# heaters.net
KiCad netlist of a schematic drawn in EAGLE
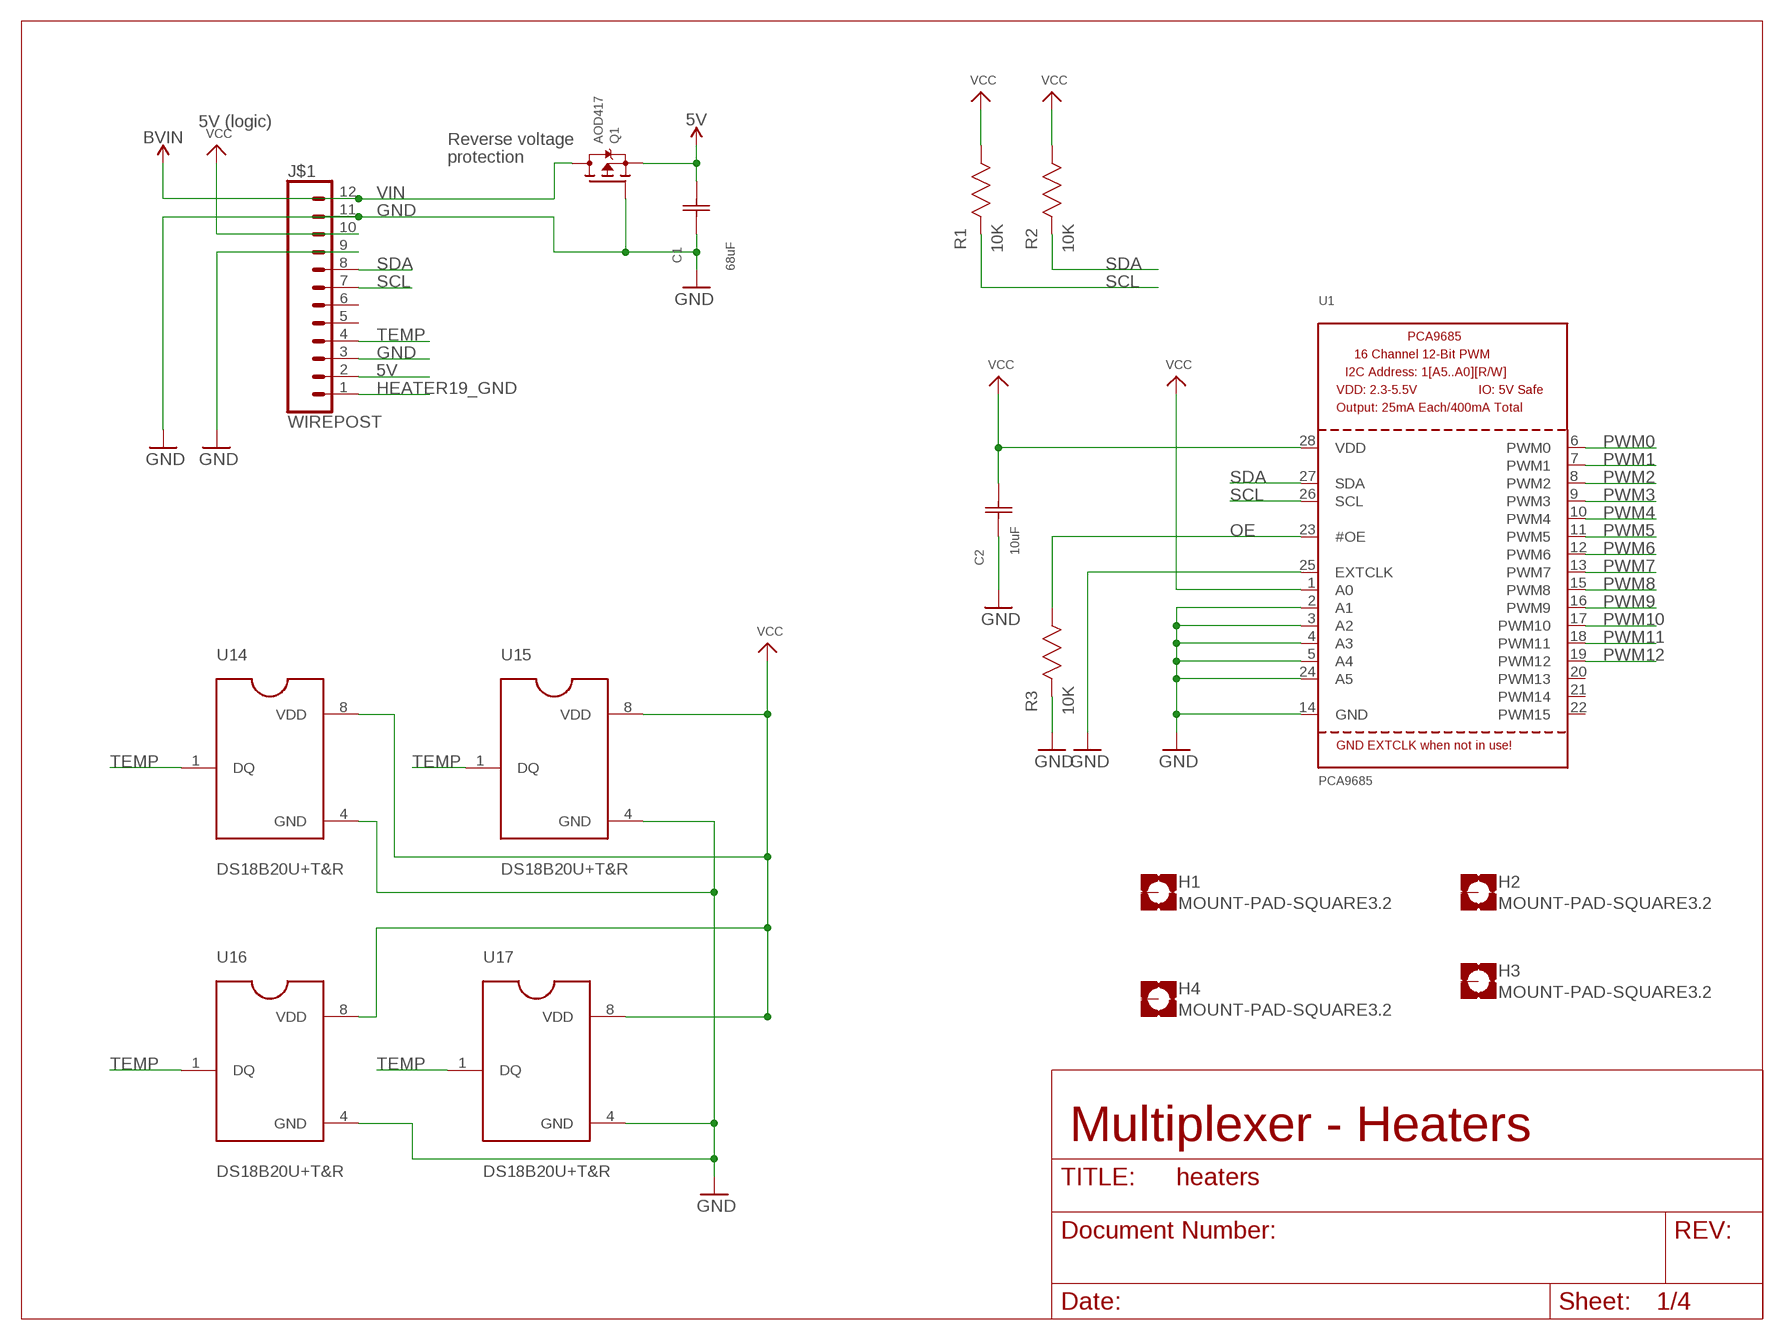
[diagram p0: schematic, sheet 1]
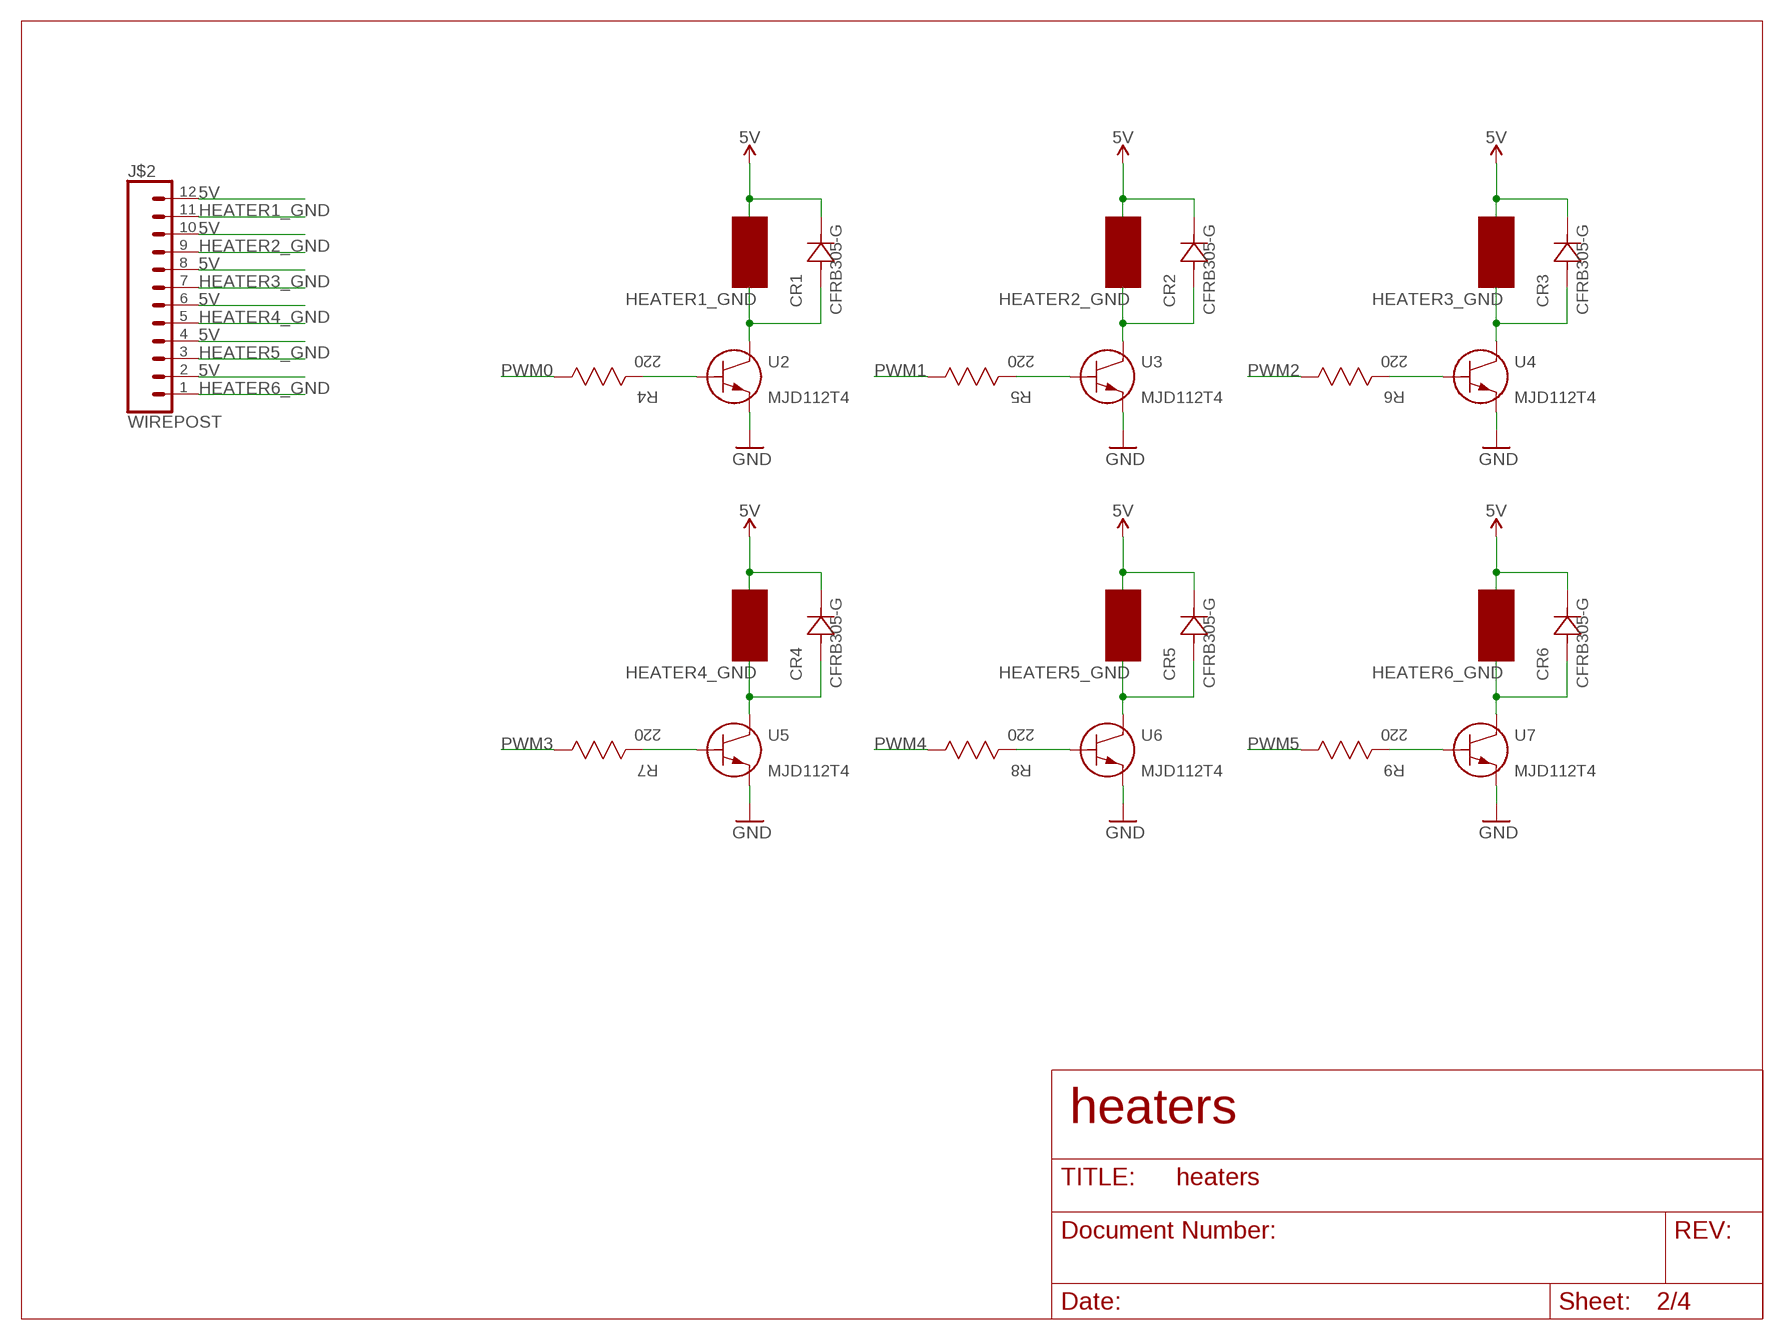
[diagram p1: schematic, sheet 2]
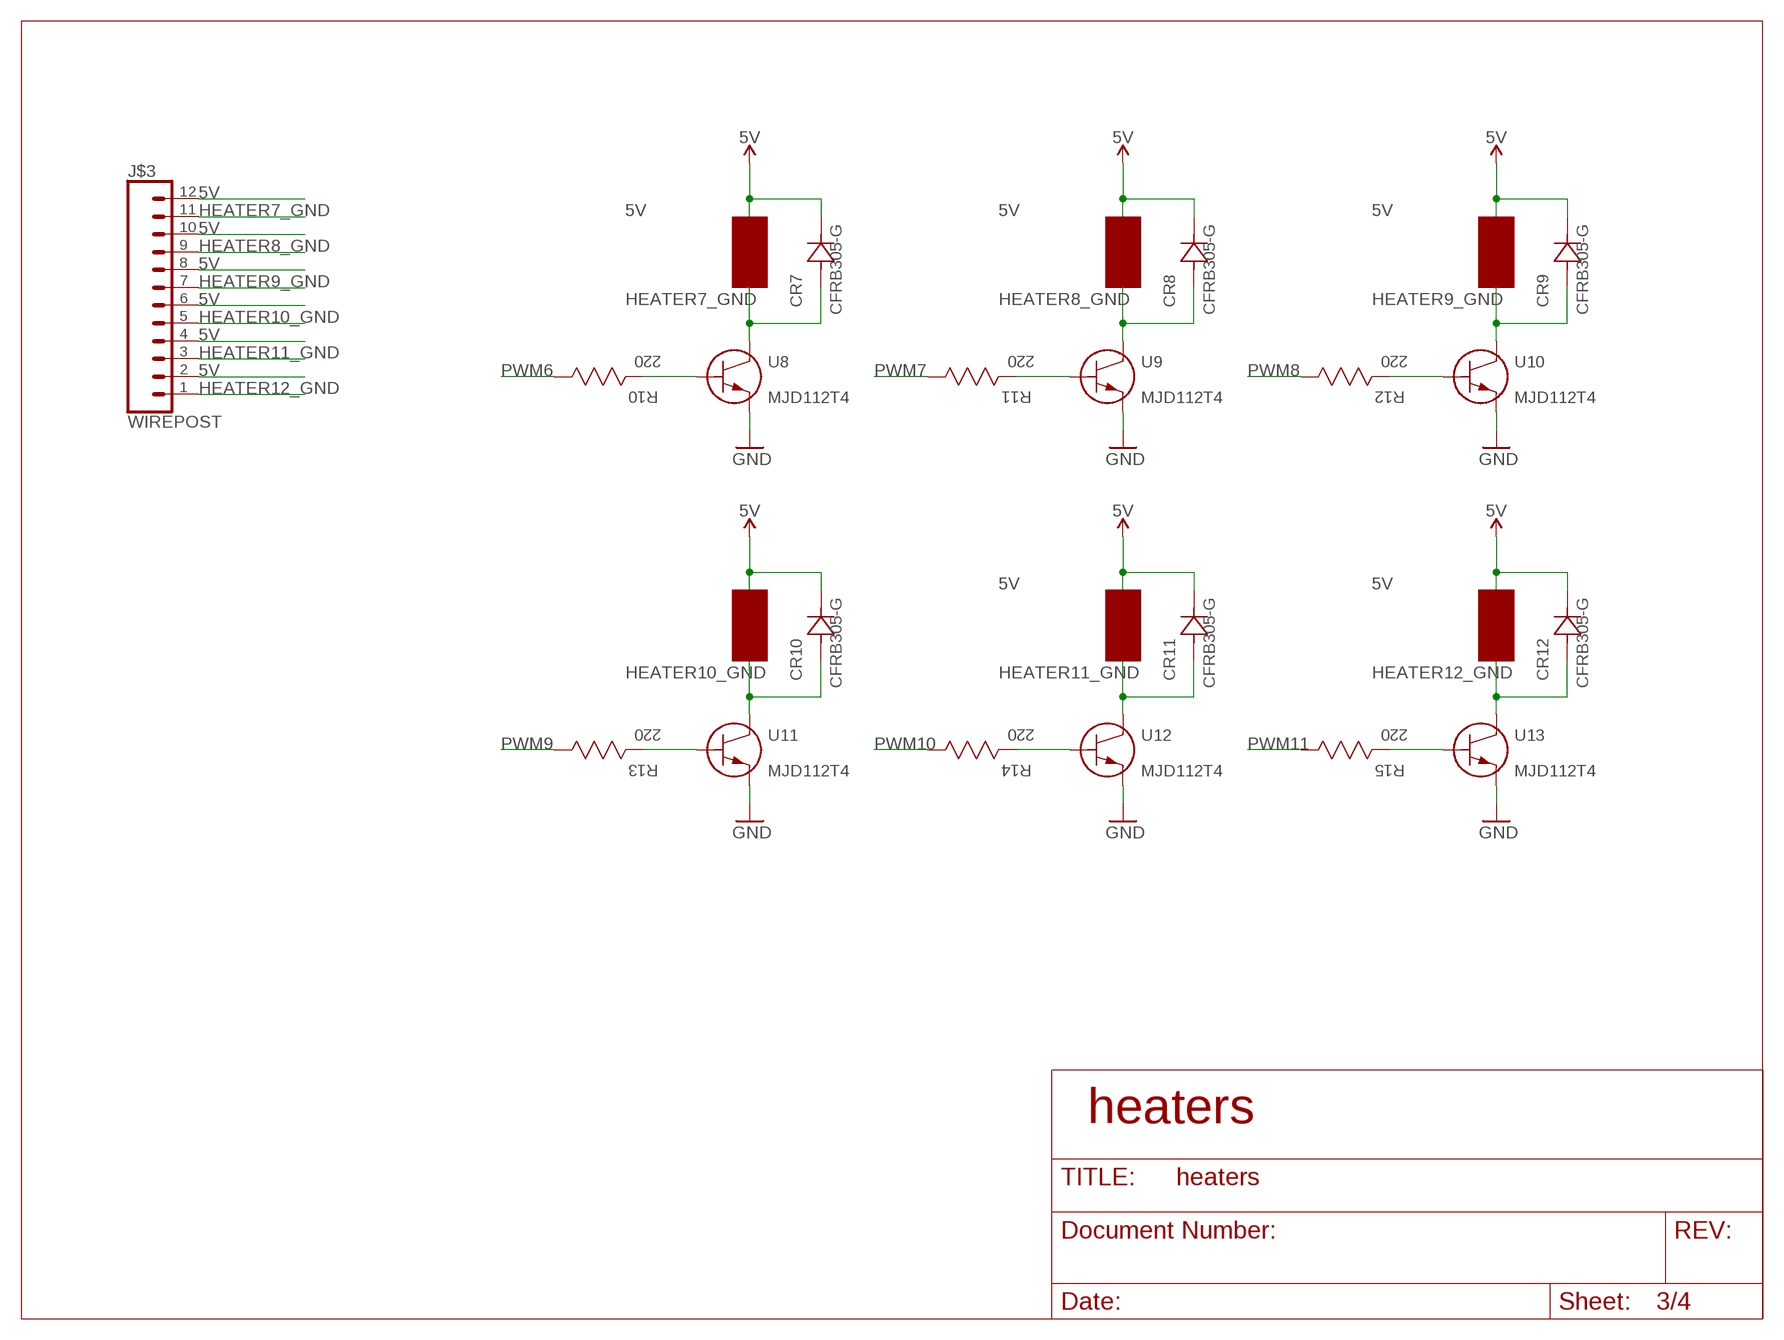
[diagram p2: schematic, sheet 3]
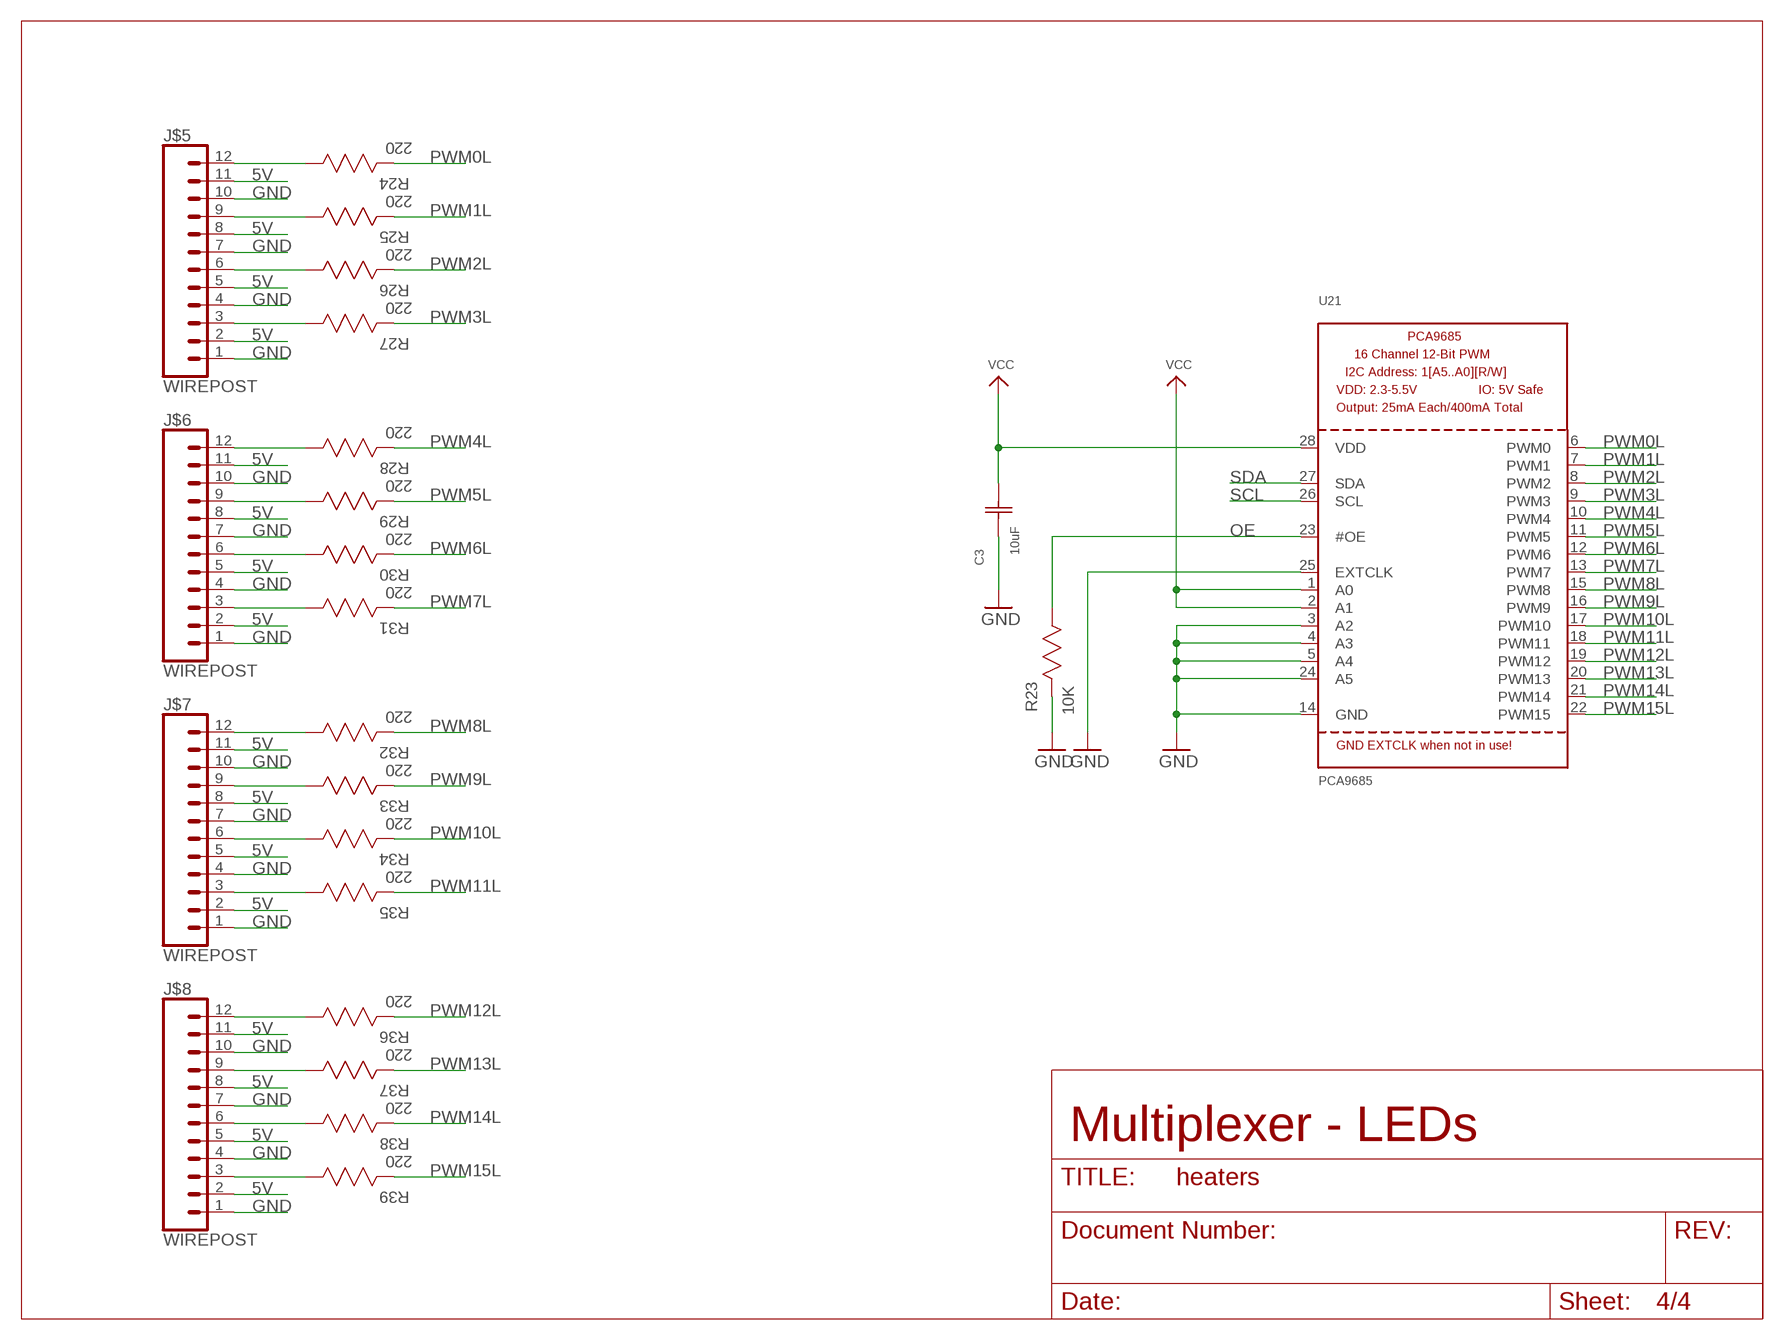
[diagram p3: schematic, sheet 4]

(export (version "E")
  (design (tool "Eeschema 10.0.6"))
  (components
    (comp (ref "C1")
      (value "68uF")
      (footprint "eagle-import:CAP_5750")
      (fields (field (name "MANUFACTURER_PART_NUMBER") "C5750X5R1A686M230KA"))
      (libsource (lib "eagle-import") (part "C5750X5R1A686M230KA"))
    )
    (comp (ref "C2")
      (value "10uF")
      (footprint "eagle-import:1206")
      (fields (field (name "MANUFACTURER_PART_NUMBER") "1206YC106KAT2A"))
      (libsource (lib "eagle-import") (part "1206YC106KAT2A"))
    )
    (comp (ref "H1")
      (value "MOUNT-PAD-SQUARE3.2")
      (footprint "eagle-import:3,2-PAD-SQUARE")
      (libsource (lib "eagle-import") (part "MOUNT-PAD-SQUARE3.2"))
    )
    (comp (ref "H2")
      (value "MOUNT-PAD-SQUARE3.2")
      (footprint "eagle-import:3,2-PAD-SQUARE")
      (libsource (lib "eagle-import") (part "MOUNT-PAD-SQUARE3.2"))
    )
    (comp (ref "H3")
      (value "MOUNT-PAD-SQUARE3.2")
      (footprint "eagle-import:3,2-PAD-SQUARE")
      (libsource (lib "eagle-import") (part "MOUNT-PAD-SQUARE3.2"))
    )
    (comp (ref "H4")
      (value "MOUNT-PAD-SQUARE3.2")
      (footprint "eagle-import:3,2-PAD-SQUARE")
      (libsource (lib "eagle-import") (part "MOUNT-PAD-SQUARE3.2"))
    )
    (comp (ref "J$1")
      (value "WIREPOST")
      (footprint "eagle-import:WIREWRAPPOST")
      (libsource (lib "eagle-import") (part "WIREPOST"))
    )
    (comp (ref "Q1")
      (value "AOD417")
      (footprint "eagle-import:TO252")
      (libsource (lib "eagle-import") (part "MOSFET-PTO252"))
    )
    (comp (ref "R1")
      (value "10K")
      (footprint "eagle-import:RC0603N")
      (fields (field (name "MANUFACTURER_PART_NUMBER") "RC0603JR0710KL"))
      (libsource (lib "eagle-import") (part "RC0603JR-0710KL"))
    )
    (comp (ref "R2")
      (value "10K")
      (footprint "eagle-import:RC0603N")
      (fields (field (name "MANUFACTURER_PART_NUMBER") "RC0603JR0710KL"))
      (libsource (lib "eagle-import") (part "RC0603JR-0710KL"))
    )
    (comp (ref "R3")
      (value "10K")
      (footprint "eagle-import:RC0603N")
      (fields (field (name "MANUFACTURER_PART_NUMBER") "RC0603JR0710KL"))
      (libsource (lib "eagle-import") (part "RC0603JR-0710KL"))
    )
    (comp (ref "U1")
      (value "PCA9685")
      (footprint "eagle-import:TSSOP28")
      (libsource (lib "eagle-import") (part "PCA9685"))
    )
    (comp (ref "U14")
      (value "DS18B20U+T&R")
      (footprint "eagle-import:SOP65P500X110-8N")
      (fields (field (name "MF") "Maxim Integrated") (field (name "MP") "DS18B20U+T&amp;R"))
      (libsource (lib "eagle-import") (part "DS18B20U+T&R"))
    )
    (comp (ref "U15")
      (value "DS18B20U+T&R")
      (footprint "eagle-import:SOP65P500X110-8N")
      (fields (field (name "MF") "Maxim Integrated") (field (name "MP") "DS18B20U+T&amp;R"))
      (libsource (lib "eagle-import") (part "DS18B20U+T&R"))
    )
    (comp (ref "U16")
      (value "DS18B20U+T&R")
      (footprint "eagle-import:SOP65P500X110-8N")
      (fields (field (name "MF") "Maxim Integrated") (field (name "MP") "DS18B20U+T&amp;R"))
      (libsource (lib "eagle-import") (part "DS18B20U+T&R"))
    )
    (comp (ref "U17")
      (value "DS18B20U+T&R")
      (footprint "eagle-import:SOP65P500X110-8N")
      (fields (field (name "MF") "Maxim Integrated") (field (name "MP") "DS18B20U+T&amp;R"))
      (libsource (lib "eagle-import") (part "DS18B20U+T&R"))
    )
    (comp (ref "C3")
      (value "10uF")
      (footprint "eagle-import:1206")
      (fields (field (name "MANUFACTURER_PART_NUMBER") "1206YC106KAT2A"))
      (libsource (lib "eagle-import") (part "1206YC106KAT2A"))
    )
    (comp (ref "J$5")
      (value "WIREPOST")
      (footprint "eagle-import:WIREWRAPPOST")
      (libsource (lib "eagle-import") (part "WIREPOST"))
    )
    (comp (ref "J$6")
      (value "WIREPOST")
      (footprint "eagle-import:WIREWRAPPOST")
      (libsource (lib "eagle-import") (part "WIREPOST"))
    )
    (comp (ref "J$7")
      (value "WIREPOST")
      (footprint "eagle-import:WIREWRAPPOST")
      (libsource (lib "eagle-import") (part "WIREPOST"))
    )
    (comp (ref "J$8")
      (value "WIREPOST")
      (footprint "eagle-import:WIREWRAPPOST")
      (libsource (lib "eagle-import") (part "WIREPOST"))
    )
    (comp (ref "R23")
      (value "10K")
      (footprint "eagle-import:RC0603N")
      (fields (field (name "MANUFACTURER_PART_NUMBER") "RC0603JR0710KL"))
      (libsource (lib "eagle-import") (part "RC0603JR-0710KL"))
    )
    (comp (ref "R24")
      (value "220")
      (footprint "eagle-import:RC0603N")
      (fields (field (name "MANUFACTURER_PART_NUMBER") "RC0603JR07220RL"))
      (libsource (lib "eagle-import") (part "RC0603JR-07220RL"))
    )
    (comp (ref "R25")
      (value "220")
      (footprint "eagle-import:RC0603N")
      (fields (field (name "MANUFACTURER_PART_NUMBER") "RC0603JR07220RL"))
      (libsource (lib "eagle-import") (part "RC0603JR-07220RL"))
    )
    (comp (ref "R26")
      (value "220")
      (footprint "eagle-import:RC0603N")
      (fields (field (name "MANUFACTURER_PART_NUMBER") "RC0603JR07220RL"))
      (libsource (lib "eagle-import") (part "RC0603JR-07220RL"))
    )
    (comp (ref "R27")
      (value "220")
      (footprint "eagle-import:RC0603N")
      (fields (field (name "MANUFACTURER_PART_NUMBER") "RC0603JR07220RL"))
      (libsource (lib "eagle-import") (part "RC0603JR-07220RL"))
    )
    (comp (ref "R28")
      (value "220")
      (footprint "eagle-import:RC0603N")
      (fields (field (name "MANUFACTURER_PART_NUMBER") "RC0603JR07220RL"))
      (libsource (lib "eagle-import") (part "RC0603JR-07220RL"))
    )
    (comp (ref "R29")
      (value "220")
      (footprint "eagle-import:RC0603N")
      (fields (field (name "MANUFACTURER_PART_NUMBER") "RC0603JR07220RL"))
      (libsource (lib "eagle-import") (part "RC0603JR-07220RL"))
    )
    (comp (ref "R30")
      (value "220")
      (footprint "eagle-import:RC0603N")
      (fields (field (name "MANUFACTURER_PART_NUMBER") "RC0603JR07220RL"))
      (libsource (lib "eagle-import") (part "RC0603JR-07220RL"))
    )
    (comp (ref "R31")
      (value "220")
      (footprint "eagle-import:RC0603N")
      (fields (field (name "MANUFACTURER_PART_NUMBER") "RC0603JR07220RL"))
      (libsource (lib "eagle-import") (part "RC0603JR-07220RL"))
    )
    (comp (ref "R32")
      (value "220")
      (footprint "eagle-import:RC0603N")
      (fields (field (name "MANUFACTURER_PART_NUMBER") "RC0603JR07220RL"))
      (libsource (lib "eagle-import") (part "RC0603JR-07220RL"))
    )
    (comp (ref "R33")
      (value "220")
      (footprint "eagle-import:RC0603N")
      (fields (field (name "MANUFACTURER_PART_NUMBER") "RC0603JR07220RL"))
      (libsource (lib "eagle-import") (part "RC0603JR-07220RL"))
    )
    (comp (ref "R34")
      (value "220")
      (footprint "eagle-import:RC0603N")
      (fields (field (name "MANUFACTURER_PART_NUMBER") "RC0603JR07220RL"))
      (libsource (lib "eagle-import") (part "RC0603JR-07220RL"))
    )
    (comp (ref "R35")
      (value "220")
      (footprint "eagle-import:RC0603N")
      (fields (field (name "MANUFACTURER_PART_NUMBER") "RC0603JR07220RL"))
      (libsource (lib "eagle-import") (part "RC0603JR-07220RL"))
    )
    (comp (ref "R36")
      (value "220")
      (footprint "eagle-import:RC0603N")
      (fields (field (name "MANUFACTURER_PART_NUMBER") "RC0603JR07220RL"))
      (libsource (lib "eagle-import") (part "RC0603JR-07220RL"))
    )
    (comp (ref "R37")
      (value "220")
      (footprint "eagle-import:RC0603N")
      (fields (field (name "MANUFACTURER_PART_NUMBER") "RC0603JR07220RL"))
      (libsource (lib "eagle-import") (part "RC0603JR-07220RL"))
    )
    (comp (ref "R38")
      (value "220")
      (footprint "eagle-import:RC0603N")
      (fields (field (name "MANUFACTURER_PART_NUMBER") "RC0603JR07220RL"))
      (libsource (lib "eagle-import") (part "RC0603JR-07220RL"))
    )
    (comp (ref "R39")
      (value "220")
      (footprint "eagle-import:RC0603N")
      (fields (field (name "MANUFACTURER_PART_NUMBER") "RC0603JR07220RL"))
      (libsource (lib "eagle-import") (part "RC0603JR-07220RL"))
    )
    (comp (ref "U21")
      (value "PCA9685")
      (footprint "eagle-import:TSSOP28")
      (libsource (lib "eagle-import") (part "PCA9685"))
    )
    (comp (ref "CR7")
      (value "CFRB305-G")
      (footprint "eagle-import:CFRB-G")
      (fields (field (name "MANUFACTURER_PART_NUMBER") "CFRB305G"))
      (libsource (lib "eagle-import") (part "CFRB305-G"))
    )
    (comp (ref "CR8")
      (value "CFRB305-G")
      (footprint "eagle-import:CFRB-G")
      (fields (field (name "MANUFACTURER_PART_NUMBER") "CFRB305G"))
      (libsource (lib "eagle-import") (part "CFRB305-G"))
    )
    (comp (ref "CR9")
      (value "CFRB305-G")
      (footprint "eagle-import:CFRB-G")
      (fields (field (name "MANUFACTURER_PART_NUMBER") "CFRB305G"))
      (libsource (lib "eagle-import") (part "CFRB305-G"))
    )
    (comp (ref "CR10")
      (value "CFRB305-G")
      (footprint "eagle-import:CFRB-G")
      (fields (field (name "MANUFACTURER_PART_NUMBER") "CFRB305G"))
      (libsource (lib "eagle-import") (part "CFRB305-G"))
    )
    (comp (ref "CR11")
      (value "CFRB305-G")
      (footprint "eagle-import:CFRB-G")
      (fields (field (name "MANUFACTURER_PART_NUMBER") "CFRB305G"))
      (libsource (lib "eagle-import") (part "CFRB305-G"))
    )
    (comp (ref "CR12")
      (value "CFRB305-G")
      (footprint "eagle-import:CFRB-G")
      (fields (field (name "MANUFACTURER_PART_NUMBER") "CFRB305G"))
      (libsource (lib "eagle-import") (part "CFRB305-G"))
    )
    (comp (ref "J$3")
      (value "WIREPOST")
      (footprint "eagle-import:WIREWRAPPOST")
      (libsource (lib "eagle-import") (part "WIREPOST"))
    )
    (comp (ref "R10")
      (value "220")
      (footprint "eagle-import:RC0603N")
      (fields (field (name "MANUFACTURER_PART_NUMBER") "RC0603JR07220RL"))
      (libsource (lib "eagle-import") (part "RC0603JR-07220RL"))
    )
    (comp (ref "R11")
      (value "220")
      (footprint "eagle-import:RC0603N")
      (fields (field (name "MANUFACTURER_PART_NUMBER") "RC0603JR07220RL"))
      (libsource (lib "eagle-import") (part "RC0603JR-07220RL"))
    )
    (comp (ref "R12")
      (value "220")
      (footprint "eagle-import:RC0603N")
      (fields (field (name "MANUFACTURER_PART_NUMBER") "RC0603JR07220RL"))
      (libsource (lib "eagle-import") (part "RC0603JR-07220RL"))
    )
    (comp (ref "R13")
      (value "220")
      (footprint "eagle-import:RC0603N")
      (fields (field (name "MANUFACTURER_PART_NUMBER") "RC0603JR07220RL"))
      (libsource (lib "eagle-import") (part "RC0603JR-07220RL"))
    )
    (comp (ref "R14")
      (value "220")
      (footprint "eagle-import:RC0603N")
      (fields (field (name "MANUFACTURER_PART_NUMBER") "RC0603JR07220RL"))
      (libsource (lib "eagle-import") (part "RC0603JR-07220RL"))
    )
    (comp (ref "R15")
      (value "220")
      (footprint "eagle-import:RC0603N")
      (fields (field (name "MANUFACTURER_PART_NUMBER") "RC0603JR07220RL"))
      (libsource (lib "eagle-import") (part "RC0603JR-07220RL"))
    )
    (comp (ref "U8")
      (value "MJD112T4")
      (footprint "eagle-import:DPAK")
      (libsource (lib "eagle-import") (part "MJD112T4"))
    )
    (comp (ref "U9")
      (value "MJD112T4")
      (footprint "eagle-import:DPAK")
      (libsource (lib "eagle-import") (part "MJD112T4"))
    )
    (comp (ref "U10")
      (value "MJD112T4")
      (footprint "eagle-import:DPAK")
      (libsource (lib "eagle-import") (part "MJD112T4"))
    )
    (comp (ref "U11")
      (value "MJD112T4")
      (footprint "eagle-import:DPAK")
      (libsource (lib "eagle-import") (part "MJD112T4"))
    )
    (comp (ref "U12")
      (value "MJD112T4")
      (footprint "eagle-import:DPAK")
      (libsource (lib "eagle-import") (part "MJD112T4"))
    )
    (comp (ref "U13")
      (value "MJD112T4")
      (footprint "eagle-import:DPAK")
      (libsource (lib "eagle-import") (part "MJD112T4"))
    )
    (comp (ref "CR1")
      (value "CFRB305-G")
      (footprint "eagle-import:CFRB-G")
      (fields (field (name "MANUFACTURER_PART_NUMBER") "CFRB305G"))
      (libsource (lib "eagle-import") (part "CFRB305-G"))
    )
    (comp (ref "CR2")
      (value "CFRB305-G")
      (footprint "eagle-import:CFRB-G")
      (fields (field (name "MANUFACTURER_PART_NUMBER") "CFRB305G"))
      (libsource (lib "eagle-import") (part "CFRB305-G"))
    )
    (comp (ref "CR3")
      (value "CFRB305-G")
      (footprint "eagle-import:CFRB-G")
      (fields (field (name "MANUFACTURER_PART_NUMBER") "CFRB305G"))
      (libsource (lib "eagle-import") (part "CFRB305-G"))
    )
    (comp (ref "CR4")
      (value "CFRB305-G")
      (footprint "eagle-import:CFRB-G")
      (fields (field (name "MANUFACTURER_PART_NUMBER") "CFRB305G"))
      (libsource (lib "eagle-import") (part "CFRB305-G"))
    )
    (comp (ref "CR5")
      (value "CFRB305-G")
      (footprint "eagle-import:CFRB-G")
      (fields (field (name "MANUFACTURER_PART_NUMBER") "CFRB305G"))
      (libsource (lib "eagle-import") (part "CFRB305-G"))
    )
    (comp (ref "CR6")
      (value "CFRB305-G")
      (footprint "eagle-import:CFRB-G")
      (fields (field (name "MANUFACTURER_PART_NUMBER") "CFRB305G"))
      (libsource (lib "eagle-import") (part "CFRB305-G"))
    )
    (comp (ref "J$2")
      (value "WIREPOST")
      (footprint "eagle-import:WIREWRAPPOST")
      (libsource (lib "eagle-import") (part "WIREPOST"))
    )
    (comp (ref "R4")
      (value "220")
      (footprint "eagle-import:RC0603N")
      (fields (field (name "MANUFACTURER_PART_NUMBER") "RC0603JR07220RL"))
      (libsource (lib "eagle-import") (part "RC0603JR-07220RL"))
    )
    (comp (ref "R5")
      (value "220")
      (footprint "eagle-import:RC0603N")
      (fields (field (name "MANUFACTURER_PART_NUMBER") "RC0603JR07220RL"))
      (libsource (lib "eagle-import") (part "RC0603JR-07220RL"))
    )
    (comp (ref "R6")
      (value "220")
      (footprint "eagle-import:RC0603N")
      (fields (field (name "MANUFACTURER_PART_NUMBER") "RC0603JR07220RL"))
      (libsource (lib "eagle-import") (part "RC0603JR-07220RL"))
    )
    (comp (ref "R7")
      (value "220")
      (footprint "eagle-import:RC0603N")
      (fields (field (name "MANUFACTURER_PART_NUMBER") "RC0603JR07220RL"))
      (libsource (lib "eagle-import") (part "RC0603JR-07220RL"))
    )
    (comp (ref "R8")
      (value "220")
      (footprint "eagle-import:RC0603N")
      (fields (field (name "MANUFACTURER_PART_NUMBER") "RC0603JR07220RL"))
      (libsource (lib "eagle-import") (part "RC0603JR-07220RL"))
    )
    (comp (ref "R9")
      (value "220")
      (footprint "eagle-import:RC0603N")
      (fields (field (name "MANUFACTURER_PART_NUMBER") "RC0603JR07220RL"))
      (libsource (lib "eagle-import") (part "RC0603JR-07220RL"))
    )
    (comp (ref "U2")
      (value "MJD112T4")
      (footprint "eagle-import:DPAK")
      (libsource (lib "eagle-import") (part "MJD112T4"))
    )
    (comp (ref "U3")
      (value "MJD112T4")
      (footprint "eagle-import:DPAK")
      (libsource (lib "eagle-import") (part "MJD112T4"))
    )
    (comp (ref "U4")
      (value "MJD112T4")
      (footprint "eagle-import:DPAK")
      (libsource (lib "eagle-import") (part "MJD112T4"))
    )
    (comp (ref "U5")
      (value "MJD112T4")
      (footprint "eagle-import:DPAK")
      (libsource (lib "eagle-import") (part "MJD112T4"))
    )
    (comp (ref "U6")
      (value "MJD112T4")
      (footprint "eagle-import:DPAK")
      (libsource (lib "eagle-import") (part "MJD112T4"))
    )
    (comp (ref "U7")
      (value "MJD112T4")
      (footprint "eagle-import:DPAK")
      (libsource (lib "eagle-import") (part "MJD112T4"))
    )
  )
  (nets
    (net (code "1") (name "5V") (class "Default")
      (node (ref "C1") (pin "2") (pinfunction "22_2") (pintype "passive"))
      (node (ref "CR1") (pin "1") (pinfunction "2_1") (pintype "passive"))
      (node (ref "CR10") (pin "1") (pinfunction "2_1") (pintype "passive"))
      (node (ref "CR11") (pin "1") (pinfunction "2_1") (pintype "passive"))
      (node (ref "CR12") (pin "1") (pinfunction "2_1") (pintype "passive"))
      (node (ref "CR2") (pin "1") (pinfunction "2_1") (pintype "passive"))
      (node (ref "CR3") (pin "1") (pinfunction "2_1") (pintype "passive"))
      (node (ref "CR4") (pin "1") (pinfunction "2_1") (pintype "passive"))
      (node (ref "CR5") (pin "1") (pinfunction "2_1") (pintype "passive"))
      (node (ref "CR6") (pin "1") (pinfunction "2_1") (pintype "passive"))
      (node (ref "CR7") (pin "1") (pinfunction "2_1") (pintype "passive"))
      (node (ref "CR8") (pin "1") (pinfunction "2_1") (pintype "passive"))
      (node (ref "CR9") (pin "1") (pinfunction "2_1") (pintype "passive"))
      (node (ref "J$1") (pin "2") (pinfunction "2_2") (pintype "passive"))
      (node (ref "J$2") (pin "10") (pinfunction "10_10") (pintype "passive"))
      (node (ref "J$2") (pin "12") (pinfunction "12_12") (pintype "passive"))
      (node (ref "J$2") (pin "2") (pinfunction "2_2") (pintype "passive"))
      (node (ref "J$2") (pin "4") (pinfunction "4_4") (pintype "passive"))
      (node (ref "J$2") (pin "6") (pinfunction "6_6") (pintype "passive"))
      (node (ref "J$2") (pin "8") (pinfunction "8_8") (pintype "passive"))
      (node (ref "J$3") (pin "10") (pinfunction "10_10") (pintype "passive"))
      (node (ref "J$3") (pin "12") (pinfunction "12_12") (pintype "passive"))
      (node (ref "J$3") (pin "2") (pinfunction "2_2") (pintype "passive"))
      (node (ref "J$3") (pin "4") (pinfunction "4_4") (pintype "passive"))
      (node (ref "J$3") (pin "6") (pinfunction "6_6") (pintype "passive"))
      (node (ref "J$3") (pin "8") (pinfunction "8_8") (pintype "passive"))
      (node (ref "J$5") (pin "11") (pinfunction "11_11") (pintype "passive"))
      (node (ref "J$5") (pin "2") (pinfunction "2_2") (pintype "passive"))
      (node (ref "J$5") (pin "5") (pinfunction "5_5") (pintype "passive"))
      (node (ref "J$5") (pin "8") (pinfunction "8_8") (pintype "passive"))
      (node (ref "J$6") (pin "11") (pinfunction "11_11") (pintype "passive"))
      (node (ref "J$6") (pin "2") (pinfunction "2_2") (pintype "passive"))
      (node (ref "J$6") (pin "5") (pinfunction "5_5") (pintype "passive"))
      (node (ref "J$6") (pin "8") (pinfunction "8_8") (pintype "passive"))
      (node (ref "J$7") (pin "11") (pinfunction "11_11") (pintype "passive"))
      (node (ref "J$7") (pin "2") (pinfunction "2_2") (pintype "passive"))
      (node (ref "J$7") (pin "5") (pinfunction "5_5") (pintype "passive"))
      (node (ref "J$7") (pin "8") (pinfunction "8_8") (pintype "passive"))
      (node (ref "J$8") (pin "11") (pinfunction "11_11") (pintype "passive"))
      (node (ref "J$8") (pin "2") (pinfunction "2_2") (pintype "passive"))
      (node (ref "J$8") (pin "5") (pinfunction "5_5") (pintype "passive"))
      (node (ref "J$8") (pin "8") (pinfunction "8_8") (pintype "passive"))
      (node (ref "Q1") (pin "2") (pinfunction "S_2") (pintype "passive"))
    )
    (net (code "2") (name "GND") (class "Default")
      (node (ref "C1") (pin "1") (pinfunction "11_1") (pintype "passive"))
      (node (ref "C2") (pin "1") (pinfunction "1_1") (pintype "passive"))
      (node (ref "C3") (pin "1") (pinfunction "1_1") (pintype "passive"))
      (node (ref "J$1") (pin "11") (pinfunction "11_11") (pintype "passive"))
      (node (ref "J$1") (pin "3") (pinfunction "3_3") (pintype "passive"))
      (node (ref "J$1") (pin "9") (pinfunction "9_9") (pintype "passive"))
      (node (ref "J$5") (pin "1") (pinfunction "1_1") (pintype "passive"))
      (node (ref "J$5") (pin "10") (pinfunction "10_10") (pintype "passive"))
      (node (ref "J$5") (pin "4") (pinfunction "4_4") (pintype "passive"))
      (node (ref "J$5") (pin "7") (pinfunction "7_7") (pintype "passive"))
      (node (ref "J$6") (pin "1") (pinfunction "1_1") (pintype "passive"))
      (node (ref "J$6") (pin "10") (pinfunction "10_10") (pintype "passive"))
      (node (ref "J$6") (pin "4") (pinfunction "4_4") (pintype "passive"))
      (node (ref "J$6") (pin "7") (pinfunction "7_7") (pintype "passive"))
      (node (ref "J$7") (pin "1") (pinfunction "1_1") (pintype "passive"))
      (node (ref "J$7") (pin "10") (pinfunction "10_10") (pintype "passive"))
      (node (ref "J$7") (pin "4") (pinfunction "4_4") (pintype "passive"))
      (node (ref "J$7") (pin "7") (pinfunction "7_7") (pintype "passive"))
      (node (ref "J$8") (pin "1") (pinfunction "1_1") (pintype "passive"))
      (node (ref "J$8") (pin "10") (pinfunction "10_10") (pintype "passive"))
      (node (ref "J$8") (pin "4") (pinfunction "4_4") (pintype "passive"))
      (node (ref "J$8") (pin "7") (pinfunction "7_7") (pintype "passive"))
      (node (ref "Q1") (pin "1") (pinfunction "G_1") (pintype "passive"))
      (node (ref "R23") (pin "2") (pinfunction "22_2") (pintype "passive"))
      (node (ref "R3") (pin "2") (pinfunction "22_2") (pintype "passive"))
      (node (ref "U1") (pin "14") (pinfunction "GND_14") (pintype "power_in"))
      (node (ref "U1") (pin "2") (pinfunction "A1_2") (pintype "bidirectional"))
      (node (ref "U1") (pin "24") (pinfunction "A5_24") (pintype "bidirectional"))
      (node (ref "U1") (pin "25") (pinfunction "EXTCLK_25") (pintype "input"))
      (node (ref "U1") (pin "3") (pinfunction "A2_3") (pintype "bidirectional"))
      (node (ref "U1") (pin "4") (pinfunction "A3_4") (pintype "bidirectional"))
      (node (ref "U1") (pin "5") (pinfunction "A4_5") (pintype "bidirectional"))
      (node (ref "U10") (pin "2") (pinfunction "E2_2") (pintype "passive"))
      (node (ref "U11") (pin "2") (pinfunction "E2_2") (pintype "passive"))
      (node (ref "U12") (pin "2") (pinfunction "E2_2") (pintype "passive"))
      (node (ref "U13") (pin "2") (pinfunction "E2_2") (pintype "passive"))
      (node (ref "U14") (pin "4") (pinfunction "GND_4") (pintype "passive"))
      (node (ref "U15") (pin "4") (pinfunction "GND_4") (pintype "passive"))
      (node (ref "U16") (pin "4") (pinfunction "GND_4") (pintype "passive"))
      (node (ref "U17") (pin "4") (pinfunction "GND_4") (pintype "passive"))
      (node (ref "U2") (pin "2") (pinfunction "E2_2") (pintype "passive"))
      (node (ref "U21") (pin "14") (pinfunction "GND_14") (pintype "power_in"))
      (node (ref "U21") (pin "24") (pinfunction "A5_24") (pintype "bidirectional"))
      (node (ref "U21") (pin "25") (pinfunction "EXTCLK_25") (pintype "input"))
      (node (ref "U21") (pin "3") (pinfunction "A2_3") (pintype "bidirectional"))
      (node (ref "U21") (pin "4") (pinfunction "A3_4") (pintype "bidirectional"))
      (node (ref "U21") (pin "5") (pinfunction "A4_5") (pintype "bidirectional"))
      (node (ref "U3") (pin "2") (pinfunction "E2_2") (pintype "passive"))
      (node (ref "U4") (pin "2") (pinfunction "E2_2") (pintype "passive"))
      (node (ref "U5") (pin "2") (pinfunction "E2_2") (pintype "passive"))
      (node (ref "U6") (pin "2") (pinfunction "E2_2") (pintype "passive"))
      (node (ref "U7") (pin "2") (pinfunction "E2_2") (pintype "passive"))
      (node (ref "U8") (pin "2") (pinfunction "E2_2") (pintype "passive"))
      (node (ref "U9") (pin "2") (pinfunction "E2_2") (pintype "passive"))
    )
    (net (code "3") (name "HEATER1_GND") (class "Default")
      (node (ref "CR1") (pin "2") (pinfunction "1_2") (pintype "passive"))
      (node (ref "J$2") (pin "11") (pinfunction "11_11") (pintype "passive"))
      (node (ref "U2") (pin "3") (pinfunction "C3_3") (pintype "passive"))
    )
    (net (code "4") (name "HEATER2_GND") (class "Default")
      (node (ref "CR2") (pin "2") (pinfunction "1_2") (pintype "passive"))
      (node (ref "J$2") (pin "9") (pinfunction "9_9") (pintype "passive"))
      (node (ref "U3") (pin "3") (pinfunction "C3_3") (pintype "passive"))
    )
    (net (code "5") (name "HEATER3_GND") (class "Default")
      (node (ref "CR3") (pin "2") (pinfunction "1_2") (pintype "passive"))
      (node (ref "J$2") (pin "7") (pinfunction "7_7") (pintype "passive"))
      (node (ref "U4") (pin "3") (pinfunction "C3_3") (pintype "passive"))
    )
    (net (code "6") (name "HEATER4_GND") (class "Default")
      (node (ref "CR4") (pin "2") (pinfunction "1_2") (pintype "passive"))
      (node (ref "J$2") (pin "5") (pinfunction "5_5") (pintype "passive"))
      (node (ref "U5") (pin "3") (pinfunction "C3_3") (pintype "passive"))
    )
    (net (code "7") (name "HEATER5_GND") (class "Default")
      (node (ref "CR5") (pin "2") (pinfunction "1_2") (pintype "passive"))
      (node (ref "J$2") (pin "3") (pinfunction "3_3") (pintype "passive"))
      (node (ref "U6") (pin "3") (pinfunction "C3_3") (pintype "passive"))
    )
    (net (code "8") (name "HEATER6_GND") (class "Default")
      (node (ref "CR6") (pin "2") (pinfunction "1_2") (pintype "passive"))
      (node (ref "J$2") (pin "1") (pinfunction "1_1") (pintype "passive"))
      (node (ref "U7") (pin "3") (pinfunction "C3_3") (pintype "passive"))
    )
    (net (code "9") (name "HEATER7_GND") (class "Default")
      (node (ref "CR7") (pin "2") (pinfunction "1_2") (pintype "passive"))
      (node (ref "J$3") (pin "11") (pinfunction "11_11") (pintype "passive"))
      (node (ref "U8") (pin "3") (pinfunction "C3_3") (pintype "passive"))
    )
    (net (code "10") (name "HEATER8_GND") (class "Default")
      (node (ref "CR8") (pin "2") (pinfunction "1_2") (pintype "passive"))
      (node (ref "J$3") (pin "9") (pinfunction "9_9") (pintype "passive"))
      (node (ref "U9") (pin "3") (pinfunction "C3_3") (pintype "passive"))
    )
    (net (code "11") (name "HEATER9_GND") (class "Default")
      (node (ref "CR9") (pin "2") (pinfunction "1_2") (pintype "passive"))
      (node (ref "J$3") (pin "7") (pinfunction "7_7") (pintype "passive"))
      (node (ref "U10") (pin "3") (pinfunction "C3_3") (pintype "passive"))
    )
    (net (code "12") (name "HEATER10_GND") (class "Default")
      (node (ref "CR10") (pin "2") (pinfunction "1_2") (pintype "passive"))
      (node (ref "J$3") (pin "5") (pinfunction "5_5") (pintype "passive"))
      (node (ref "U11") (pin "3") (pinfunction "C3_3") (pintype "passive"))
    )
    (net (code "13") (name "HEATER11_GND") (class "Default")
      (node (ref "CR11") (pin "2") (pinfunction "1_2") (pintype "passive"))
      (node (ref "J$3") (pin "3") (pinfunction "3_3") (pintype "passive"))
      (node (ref "U12") (pin "3") (pinfunction "C3_3") (pintype "passive"))
    )
    (net (code "14") (name "HEATER12_GND") (class "Default")
      (node (ref "CR12") (pin "2") (pinfunction "1_2") (pintype "passive"))
      (node (ref "J$3") (pin "1") (pinfunction "1_1") (pintype "passive"))
      (node (ref "U13") (pin "3") (pinfunction "C3_3") (pintype "passive"))
    )
    (net (code "15") (name "HEATER19_GND") (class "Default")
      (node (ref "J$1") (pin "1") (pinfunction "1_1") (pintype "passive"))
    )
    (net (code "16") (name "Net-(R4-22)") (class "Default")
      (node (ref "R4") (pin "2") (pinfunction "22_2") (pintype "passive"))
      (node (ref "U2") (pin "1") (pinfunction "B1_1") (pintype "passive"))
    )
    (net (code "17") (name "Net-(R5-22)") (class "Default")
      (node (ref "R5") (pin "2") (pinfunction "22_2") (pintype "passive"))
      (node (ref "U3") (pin "1") (pinfunction "B1_1") (pintype "passive"))
    )
    (net (code "18") (name "Net-(R6-22)") (class "Default")
      (node (ref "R6") (pin "2") (pinfunction "22_2") (pintype "passive"))
      (node (ref "U4") (pin "1") (pinfunction "B1_1") (pintype "passive"))
    )
    (net (code "19") (name "Net-(R7-22)") (class "Default")
      (node (ref "R7") (pin "2") (pinfunction "22_2") (pintype "passive"))
      (node (ref "U5") (pin "1") (pinfunction "B1_1") (pintype "passive"))
    )
    (net (code "20") (name "Net-(R8-22)") (class "Default")
      (node (ref "R8") (pin "2") (pinfunction "22_2") (pintype "passive"))
      (node (ref "U6") (pin "1") (pinfunction "B1_1") (pintype "passive"))
    )
    (net (code "21") (name "Net-(R9-22)") (class "Default")
      (node (ref "R9") (pin "2") (pinfunction "22_2") (pintype "passive"))
      (node (ref "U7") (pin "1") (pinfunction "B1_1") (pintype "passive"))
    )
    (net (code "22") (name "Net-(R10-22)") (class "Default")
      (node (ref "R10") (pin "2") (pinfunction "22_2") (pintype "passive"))
      (node (ref "U8") (pin "1") (pinfunction "B1_1") (pintype "passive"))
    )
    (net (code "23") (name "Net-(R11-22)") (class "Default")
      (node (ref "R11") (pin "2") (pinfunction "22_2") (pintype "passive"))
      (node (ref "U9") (pin "1") (pinfunction "B1_1") (pintype "passive"))
    )
    (net (code "24") (name "Net-(R12-22)") (class "Default")
      (node (ref "R12") (pin "2") (pinfunction "22_2") (pintype "passive"))
      (node (ref "U10") (pin "1") (pinfunction "B1_1") (pintype "passive"))
    )
    (net (code "25") (name "Net-(R13-22)") (class "Default")
      (node (ref "R13") (pin "2") (pinfunction "22_2") (pintype "passive"))
      (node (ref "U11") (pin "1") (pinfunction "B1_1") (pintype "passive"))
    )
    (net (code "26") (name "Net-(R14-22)") (class "Default")
      (node (ref "R14") (pin "2") (pinfunction "22_2") (pintype "passive"))
      (node (ref "U12") (pin "1") (pinfunction "B1_1") (pintype "passive"))
    )
    (net (code "27") (name "Net-(R15-22)") (class "Default")
      (node (ref "R15") (pin "2") (pinfunction "22_2") (pintype "passive"))
      (node (ref "U13") (pin "1") (pinfunction "B1_1") (pintype "passive"))
    )
    (net (code "28") (name "Net-(R24-11)") (class "Default")
      (node (ref "J$5") (pin "12") (pinfunction "12_12") (pintype "passive"))
      (node (ref "R24") (pin "1") (pinfunction "11_1") (pintype "passive"))
    )
    (net (code "29") (name "Net-(R25-11)") (class "Default")
      (node (ref "J$5") (pin "9") (pinfunction "9_9") (pintype "passive"))
      (node (ref "R25") (pin "1") (pinfunction "11_1") (pintype "passive"))
    )
    (net (code "30") (name "Net-(R26-11)") (class "Default")
      (node (ref "J$5") (pin "6") (pinfunction "6_6") (pintype "passive"))
      (node (ref "R26") (pin "1") (pinfunction "11_1") (pintype "passive"))
    )
    (net (code "31") (name "Net-(R27-11)") (class "Default")
      (node (ref "J$5") (pin "3") (pinfunction "3_3") (pintype "passive"))
      (node (ref "R27") (pin "1") (pinfunction "11_1") (pintype "passive"))
    )
    (net (code "32") (name "Net-(R28-11)") (class "Default")
      (node (ref "J$6") (pin "12") (pinfunction "12_12") (pintype "passive"))
      (node (ref "R28") (pin "1") (pinfunction "11_1") (pintype "passive"))
    )
    (net (code "33") (name "Net-(R29-11)") (class "Default")
      (node (ref "J$6") (pin "9") (pinfunction "9_9") (pintype "passive"))
      (node (ref "R29") (pin "1") (pinfunction "11_1") (pintype "passive"))
    )
    (net (code "34") (name "Net-(R30-11)") (class "Default")
      (node (ref "J$6") (pin "6") (pinfunction "6_6") (pintype "passive"))
      (node (ref "R30") (pin "1") (pinfunction "11_1") (pintype "passive"))
    )
    (net (code "35") (name "Net-(R31-11)") (class "Default")
      (node (ref "J$6") (pin "3") (pinfunction "3_3") (pintype "passive"))
      (node (ref "R31") (pin "1") (pinfunction "11_1") (pintype "passive"))
    )
    (net (code "36") (name "Net-(R32-11)") (class "Default")
      (node (ref "J$7") (pin "12") (pinfunction "12_12") (pintype "passive"))
      (node (ref "R32") (pin "1") (pinfunction "11_1") (pintype "passive"))
    )
    (net (code "37") (name "Net-(R33-11)") (class "Default")
      (node (ref "J$7") (pin "9") (pinfunction "9_9") (pintype "passive"))
      (node (ref "R33") (pin "1") (pinfunction "11_1") (pintype "passive"))
    )
    (net (code "38") (name "Net-(R34-11)") (class "Default")
      (node (ref "J$7") (pin "6") (pinfunction "6_6") (pintype "passive"))
      (node (ref "R34") (pin "1") (pinfunction "11_1") (pintype "passive"))
    )
    (net (code "39") (name "Net-(R35-11)") (class "Default")
      (node (ref "J$7") (pin "3") (pinfunction "3_3") (pintype "passive"))
      (node (ref "R35") (pin "1") (pinfunction "11_1") (pintype "passive"))
    )
    (net (code "40") (name "Net-(R36-11)") (class "Default")
      (node (ref "J$8") (pin "12") (pinfunction "12_12") (pintype "passive"))
      (node (ref "R36") (pin "1") (pinfunction "11_1") (pintype "passive"))
    )
    (net (code "41") (name "Net-(R37-11)") (class "Default")
      (node (ref "J$8") (pin "9") (pinfunction "9_9") (pintype "passive"))
      (node (ref "R37") (pin "1") (pinfunction "11_1") (pintype "passive"))
    )
    (net (code "42") (name "Net-(R38-11)") (class "Default")
      (node (ref "J$8") (pin "6") (pinfunction "6_6") (pintype "passive"))
      (node (ref "R38") (pin "1") (pinfunction "11_1") (pintype "passive"))
    )
    (net (code "43") (name "Net-(R39-11)") (class "Default")
      (node (ref "J$8") (pin "3") (pinfunction "3_3") (pintype "passive"))
      (node (ref "R39") (pin "1") (pinfunction "11_1") (pintype "passive"))
    )
    (net (code "44") (name "OE") (class "Default")
      (node (ref "R23") (pin "1") (pinfunction "11_1") (pintype "passive"))
      (node (ref "R3") (pin "1") (pinfunction "11_1") (pintype "passive"))
      (node (ref "U1") (pin "23") (pinfunction "#OE_23") (pintype "input"))
      (node (ref "U21") (pin "23") (pinfunction "#OE_23") (pintype "input"))
    )
    (net (code "45") (name "PWM0") (class "Default")
      (node (ref "R4") (pin "1") (pinfunction "11_1") (pintype "passive"))
      (node (ref "U1") (pin "6") (pinfunction "PWM0_6") (pintype "output"))
    )
    (net (code "46") (name "PWM0L") (class "Default")
      (node (ref "R24") (pin "2") (pinfunction "22_2") (pintype "passive"))
      (node (ref "U21") (pin "6") (pinfunction "PWM0_6") (pintype "output"))
    )
    (net (code "47") (name "PWM1") (class "Default")
      (node (ref "R5") (pin "1") (pinfunction "11_1") (pintype "passive"))
      (node (ref "U1") (pin "7") (pinfunction "PWM1_7") (pintype "output"))
    )
    (net (code "48") (name "PWM1L") (class "Default")
      (node (ref "R25") (pin "2") (pinfunction "22_2") (pintype "passive"))
      (node (ref "U21") (pin "7") (pinfunction "PWM1_7") (pintype "output"))
    )
    (net (code "49") (name "PWM2") (class "Default")
      (node (ref "R6") (pin "1") (pinfunction "11_1") (pintype "passive"))
      (node (ref "U1") (pin "8") (pinfunction "PWM2_8") (pintype "output"))
    )
    (net (code "50") (name "PWM2L") (class "Default")
      (node (ref "R26") (pin "2") (pinfunction "22_2") (pintype "passive"))
      (node (ref "U21") (pin "8") (pinfunction "PWM2_8") (pintype "output"))
    )
    (net (code "51") (name "PWM3") (class "Default")
      (node (ref "R7") (pin "1") (pinfunction "11_1") (pintype "passive"))
      (node (ref "U1") (pin "9") (pinfunction "PWM3_9") (pintype "output"))
    )
    (net (code "52") (name "PWM3L") (class "Default")
      (node (ref "R27") (pin "2") (pinfunction "22_2") (pintype "passive"))
      (node (ref "U21") (pin "9") (pinfunction "PWM3_9") (pintype "output"))
    )
    (net (code "53") (name "PWM4") (class "Default")
      (node (ref "R8") (pin "1") (pinfunction "11_1") (pintype "passive"))
      (node (ref "U1") (pin "10") (pinfunction "PWM4_10") (pintype "output"))
    )
    (net (code "54") (name "PWM4L") (class "Default")
      (node (ref "R28") (pin "2") (pinfunction "22_2") (pintype "passive"))
      (node (ref "U21") (pin "10") (pinfunction "PWM4_10") (pintype "output"))
    )
    (net (code "55") (name "PWM5") (class "Default")
      (node (ref "R9") (pin "1") (pinfunction "11_1") (pintype "passive"))
      (node (ref "U1") (pin "11") (pinfunction "PWM5_11") (pintype "output"))
    )
    (net (code "56") (name "PWM5L") (class "Default")
      (node (ref "R29") (pin "2") (pinfunction "22_2") (pintype "passive"))
      (node (ref "U21") (pin "11") (pinfunction "PWM5_11") (pintype "output"))
    )
    (net (code "57") (name "PWM6") (class "Default")
      (node (ref "R10") (pin "1") (pinfunction "11_1") (pintype "passive"))
      (node (ref "U1") (pin "12") (pinfunction "PWM6_12") (pintype "output"))
    )
    (net (code "58") (name "PWM6L") (class "Default")
      (node (ref "R30") (pin "2") (pinfunction "22_2") (pintype "passive"))
      (node (ref "U21") (pin "12") (pinfunction "PWM6_12") (pintype "output"))
    )
    (net (code "59") (name "PWM7") (class "Default")
      (node (ref "R11") (pin "1") (pinfunction "11_1") (pintype "passive"))
      (node (ref "U1") (pin "13") (pinfunction "PWM7_13") (pintype "output"))
    )
    (net (code "60") (name "PWM7L") (class "Default")
      (node (ref "R31") (pin "2") (pinfunction "22_2") (pintype "passive"))
      (node (ref "U21") (pin "13") (pinfunction "PWM7_13") (pintype "output"))
    )
    (net (code "61") (name "PWM8") (class "Default")
      (node (ref "R12") (pin "1") (pinfunction "11_1") (pintype "passive"))
      (node (ref "U1") (pin "15") (pinfunction "PWM8_15") (pintype "output"))
    )
    (net (code "62") (name "PWM8L") (class "Default")
      (node (ref "R32") (pin "2") (pinfunction "22_2") (pintype "passive"))
      (node (ref "U21") (pin "15") (pinfunction "PWM8_15") (pintype "output"))
    )
    (net (code "63") (name "PWM9") (class "Default")
      (node (ref "R13") (pin "1") (pinfunction "11_1") (pintype "passive"))
      (node (ref "U1") (pin "16") (pinfunction "PWM9_16") (pintype "output"))
    )
    (net (code "64") (name "PWM9L") (class "Default")
      (node (ref "R33") (pin "2") (pinfunction "22_2") (pintype "passive"))
      (node (ref "U21") (pin "16") (pinfunction "PWM9_16") (pintype "output"))
    )
    (net (code "65") (name "PWM10") (class "Default")
      (node (ref "R14") (pin "1") (pinfunction "11_1") (pintype "passive"))
      (node (ref "U1") (pin "17") (pinfunction "PWM10_17") (pintype "output"))
    )
    (net (code "66") (name "PWM10L") (class "Default")
      (node (ref "R34") (pin "2") (pinfunction "22_2") (pintype "passive"))
      (node (ref "U21") (pin "17") (pinfunction "PWM10_17") (pintype "output"))
    )
    (net (code "67") (name "PWM11") (class "Default")
      (node (ref "R15") (pin "1") (pinfunction "11_1") (pintype "passive"))
      (node (ref "U1") (pin "18") (pinfunction "PWM11_18") (pintype "output"))
    )
    (net (code "68") (name "PWM11L") (class "Default")
      (node (ref "R35") (pin "2") (pinfunction "22_2") (pintype "passive"))
      (node (ref "U21") (pin "18") (pinfunction "PWM11_18") (pintype "output"))
    )
    (net (code "69") (name "PWM12") (class "Default")
      (node (ref "U1") (pin "19") (pinfunction "PWM12_19") (pintype "output"))
    )
    (net (code "70") (name "PWM12L") (class "Default")
      (node (ref "R36") (pin "2") (pinfunction "22_2") (pintype "passive"))
      (node (ref "U21") (pin "19") (pinfunction "PWM12_19") (pintype "output"))
    )
    (net (code "71") (name "PWM13L") (class "Default")
      (node (ref "R37") (pin "2") (pinfunction "22_2") (pintype "passive"))
      (node (ref "U21") (pin "20") (pinfunction "PWM13_20") (pintype "output"))
    )
    (net (code "72") (name "PWM14L") (class "Default")
      (node (ref "R38") (pin "2") (pinfunction "22_2") (pintype "passive"))
      (node (ref "U21") (pin "21") (pinfunction "PWM14_21") (pintype "output"))
    )
    (net (code "73") (name "PWM15L") (class "Default")
      (node (ref "R39") (pin "2") (pinfunction "22_2") (pintype "passive"))
      (node (ref "U21") (pin "22") (pinfunction "PWM15_22") (pintype "output"))
    )
    (net (code "74") (name "SCL") (class "Default")
      (node (ref "J$1") (pin "7") (pinfunction "7_7") (pintype "passive"))
      (node (ref "R1") (pin "2") (pinfunction "22_2") (pintype "passive"))
      (node (ref "U1") (pin "26") (pinfunction "SCL_26") (pintype "bidirectional"))
      (node (ref "U21") (pin "26") (pinfunction "SCL_26") (pintype "bidirectional"))
    )
    (net (code "75") (name "SDA") (class "Default")
      (node (ref "J$1") (pin "8") (pinfunction "8_8") (pintype "passive"))
      (node (ref "R2") (pin "2") (pinfunction "22_2") (pintype "passive"))
      (node (ref "U1") (pin "27") (pinfunction "SDA_27") (pintype "bidirectional"))
      (node (ref "U21") (pin "27") (pinfunction "SDA_27") (pintype "bidirectional"))
    )
    (net (code "76") (name "TEMP") (class "Default")
      (node (ref "J$1") (pin "4") (pinfunction "4_4") (pintype "passive"))
      (node (ref "U14") (pin "1") (pinfunction "DQ_1") (pintype "bidirectional"))
      (node (ref "U15") (pin "1") (pinfunction "DQ_1") (pintype "bidirectional"))
      (node (ref "U16") (pin "1") (pinfunction "DQ_1") (pintype "bidirectional"))
      (node (ref "U17") (pin "1") (pinfunction "DQ_1") (pintype "bidirectional"))
    )
    (net (code "77") (name "VCC") (class "Default")
      (node (ref "C2") (pin "2") (pinfunction "2_2") (pintype "passive"))
      (node (ref "C3") (pin "2") (pinfunction "2_2") (pintype "passive"))
      (node (ref "J$1") (pin "10") (pinfunction "10_10") (pintype "passive"))
      (node (ref "R1") (pin "1") (pinfunction "11_1") (pintype "passive"))
      (node (ref "R2") (pin "1") (pinfunction "11_1") (pintype "passive"))
      (node (ref "U1") (pin "1") (pinfunction "A0_1") (pintype "bidirectional"))
      (node (ref "U1") (pin "28") (pinfunction "VDD_28") (pintype "power_in"))
      (node (ref "U14") (pin "8") (pinfunction "VDD_8") (pintype "power_in"))
      (node (ref "U15") (pin "8") (pinfunction "VDD_8") (pintype "power_in"))
      (node (ref "U16") (pin "8") (pinfunction "VDD_8") (pintype "power_in"))
      (node (ref "U17") (pin "8") (pinfunction "VDD_8") (pintype "power_in"))
      (node (ref "U21") (pin "1") (pinfunction "A0_1") (pintype "bidirectional"))
      (node (ref "U21") (pin "2") (pinfunction "A1_2") (pintype "bidirectional"))
      (node (ref "U21") (pin "28") (pinfunction "VDD_28") (pintype "power_in"))
    )
    (net (code "78") (name "VIN") (class "Default")
      (node (ref "J$1") (pin "12") (pinfunction "12_12") (pintype "passive"))
      (node (ref "Q1") (pin "3") (pinfunction "D_3") (pintype "passive"))
    )
    (net (code "79") (name "unconnected-(H1-MOUNT-PadB3,2)") (class "Default")
      (node (ref "H1") (pin "B3,2") (pinfunction "MOUNT_B3,2") (pintype "passive"))
    )
    (net (code "80") (name "unconnected-(H2-MOUNT-PadB3,2)") (class "Default")
      (node (ref "H2") (pin "B3,2") (pinfunction "MOUNT_B3,2") (pintype "passive"))
    )
    (net (code "81") (name "unconnected-(H3-MOUNT-PadB3,2)") (class "Default")
      (node (ref "H3") (pin "B3,2") (pinfunction "MOUNT_B3,2") (pintype "passive"))
    )
    (net (code "82") (name "unconnected-(H4-MOUNT-PadB3,2)") (class "Default")
      (node (ref "H4") (pin "B3,2") (pinfunction "MOUNT_B3,2") (pintype "passive"))
    )
    (net (code "83") (name "unconnected-(J$1-Pad5)") (class "Default")
      (node (ref "J$1") (pin "5") (pinfunction "5_5") (pintype "passive"))
    )
    (net (code "84") (name "unconnected-(J$1-Pad6)") (class "Default")
      (node (ref "J$1") (pin "6") (pinfunction "6_6") (pintype "passive"))
    )
    (net (code "85") (name "unconnected-(U1-PWM13-Pad20)") (class "Default")
      (node (ref "U1") (pin "20") (pinfunction "PWM13_20") (pintype "output"))
    )
    (net (code "86") (name "unconnected-(U1-PWM14-Pad21)") (class "Default")
      (node (ref "U1") (pin "21") (pinfunction "PWM14_21") (pintype "output"))
    )
    (net (code "87") (name "unconnected-(U1-PWM15-Pad22)") (class "Default")
      (node (ref "U1") (pin "22") (pinfunction "PWM15_22") (pintype "output"))
    )
  )
)
